# 2019.net
KiCad netlist of a schematic drawn in Altium Designer
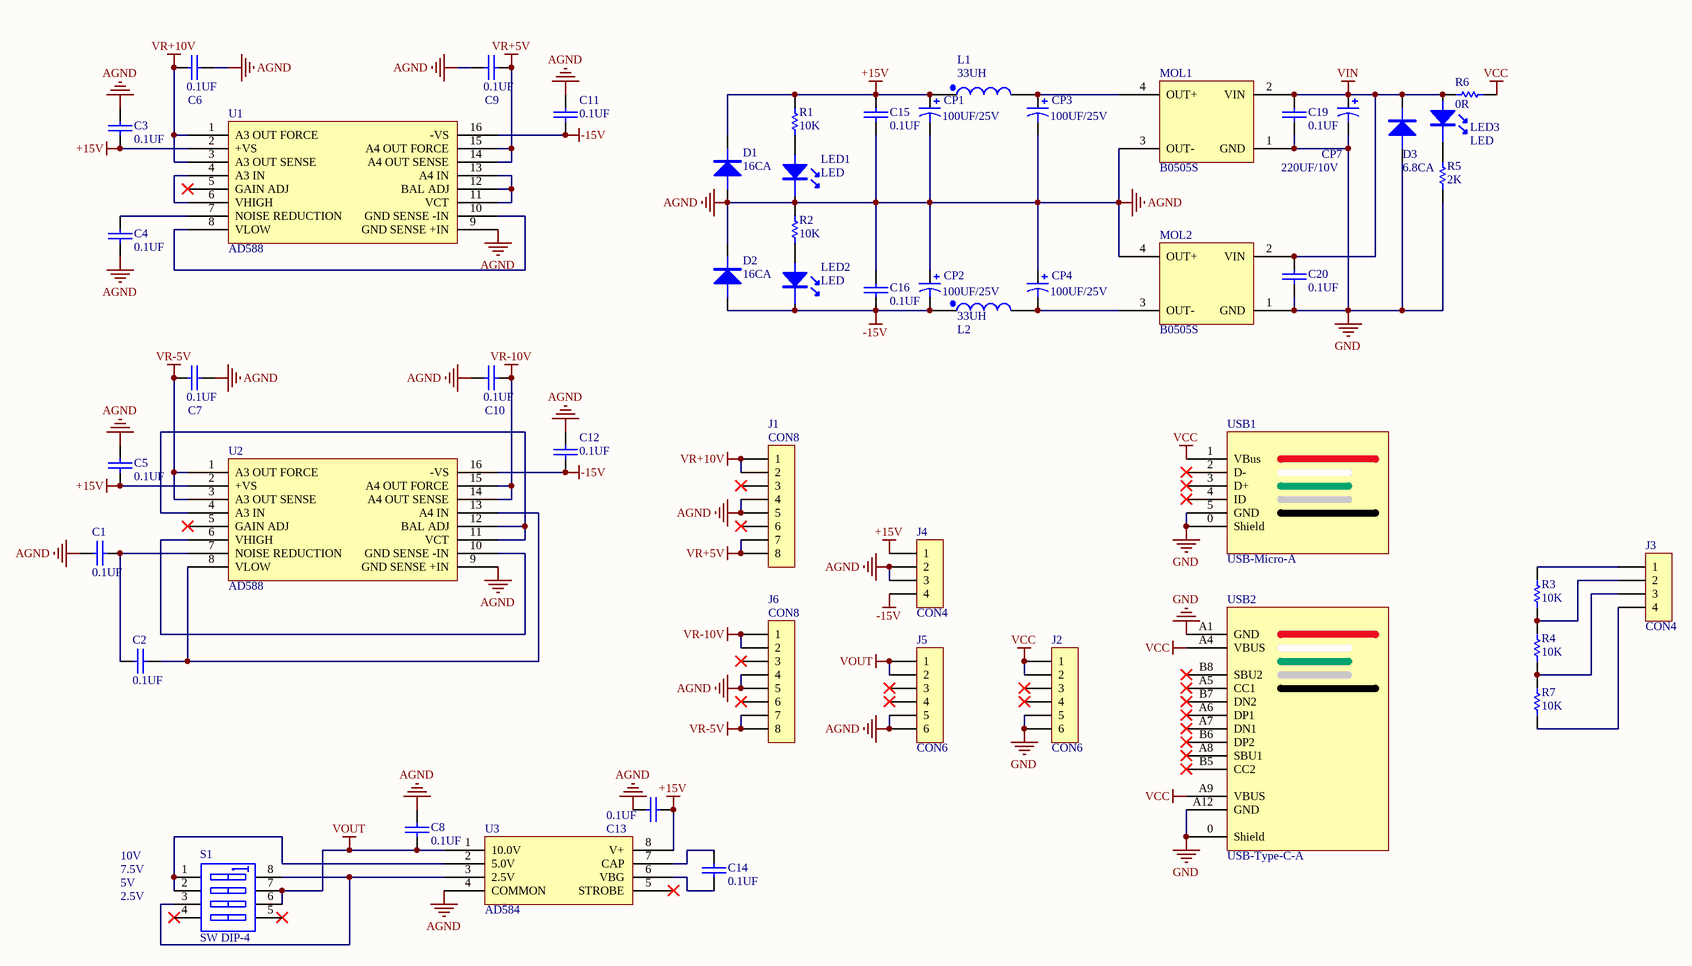
[diagram p0: 2019电压基准.SchDoc]

(export (version "E")
  (design (tool "Eeschema 10.0.6"))
  (components
    (comp (ref "C1") (value "0.1UF") (footprint "cap-3") (libsource (lib "原理图库") (part "CAP")))
    (comp (ref "C2") (value "0.1UF") (footprint "cap-3") (libsource (lib "原理图库") (part "CAP")))
    (comp (ref "C3") (value "0.1UF") (footprint "CAP-3") (libsource (lib "原理图库") (part "CAP")))
    (comp (ref "C4") (value "0.1UF") (footprint "CAP-3") (libsource (lib "原理图库") (part "CAP")))
    (comp (ref "C5") (value "0.1UF") (footprint "cap-3") (libsource (lib "原理图库") (part "CAP")))
    (comp (ref "C6") (value "0.1UF") (footprint "CAP-3") (libsource (lib "原理图库") (part "CAP")))
    (comp (ref "C7") (value "0.1UF") (footprint "CAP-3") (libsource (lib "原理图库") (part "CAP")))
    (comp (ref "C8") (value "0.1UF") (footprint "CAP-3") (libsource (lib "原理图库") (part "CAP")))
    (comp (ref "C9") (value "0.1UF") (footprint "CAP-3") (libsource (lib "原理图库") (part "CAP")))
    (comp (ref "C10") (value "0.1UF") (footprint "CAP-3") (libsource (lib "原理图库") (part "CAP")))
    (comp (ref "C11") (value "0.1UF") (footprint "CAP-3") (libsource (lib "原理图库") (part "CAP")))
    (comp (ref "C12") (value "0.1UF") (footprint "cap-3") (libsource (lib "原理图库") (part "CAP")))
    (comp (ref "C13") (value "0.1UF") (footprint "CAP-3") (libsource (lib "原理图库") (part "CAP")))
    (comp (ref "C14") (value "0.1UF") (footprint "cap-3") (libsource (lib "原理图库") (part "CAP")))
    (comp (ref "C15") (value "0.1UF") (footprint "LC-0603-C") (libsource (lib "原理图库") (part "CAP")))
    (comp (ref "C16") (value "0.1UF") (footprint "LC-0603-C") (libsource (lib "原理图库") (part "CAP")))
    (comp (ref "C19") (value "0.1UF") (footprint "LC-0603-C") (libsource (lib "原理图库") (part "CAP")))
    (comp (ref "C20") (value "0.1UF") (footprint "LC-0603-C") (libsource (lib "原理图库") (part "CAP")))
    (comp (ref "CP1") (value "100UF/25V") (footprint "cap") (libsource (lib "原理图库") (part "CAP1")))
    (comp (ref "CP2") (value "100UF/25V") (footprint "cap") (libsource (lib "原理图库") (part "CAP1")))
    (comp (ref "CP3") (value "100UF/25V") (footprint "cap") (libsource (lib "原理图库") (part "CAP1")))
    (comp (ref "CP4") (value "100UF/25V") (footprint "cap") (libsource (lib "原理图库") (part "CAP1")))
    (comp (ref "CP7") (value "220UF/10V") (footprint "cap") (libsource (lib "原理图库") (part "CAP1")))
    (comp (ref "D1")
      (value "16CA")
      (footprint "LC-SMA(DO-214AC)_S3")
      (libsource (lib "原理图库.坏") (part "DIODE"))
    )
    (comp (ref "D2")
      (value "16CA")
      (footprint "LC-SMA(DO-214AC)_S3")
      (libsource (lib "原理图库.坏") (part "DIODE"))
    )
    (comp (ref "D3")
      (value "6.8CA")
      (footprint "LC-SMA(DO-214AC)_S3")
      (libsource (lib "原理图库.坏") (part "DIODE"))
    )
    (comp (ref "J1")
      (value "CON8")
      (footprint "sip-8")
      (description "Connector")
      (libsource (lib "接插件") (part "CON8"))
    )
    (comp (ref "J2")
      (value "CON6")
      (footprint "sip-6")
      (description "Connector")
      (libsource (lib "接插件") (part "CON6"))
    )
    (comp (ref "J3")
      (value "CON4")
      (footprint "sip-4")
      (description "Connector")
      (libsource (lib "接插件") (part "CON4"))
    )
    (comp (ref "J4")
      (value "CON4")
      (footprint "sip-4")
      (description "Connector")
      (libsource (lib "接插件") (part "CON4"))
    )
    (comp (ref "J5")
      (value "CON6")
      (footprint "sip-6")
      (description "Connector")
      (libsource (lib "接插件") (part "CON6"))
    )
    (comp (ref "J6")
      (value "CON8")
      (footprint "sip-8")
      (description "Connector")
      (libsource (lib "接插件") (part "CON8"))
    )
    (comp (ref "L1") (value "33UH") (footprint "lin6*6") (libsource (lib "原理图库") (part "INDUCTOR")))
    (comp (ref "L2") (value "33UH") (footprint "lin6*6") (libsource (lib "原理图库") (part "INDUCTOR")))
    (comp (ref "LED1") (value "LED") (footprint "lc-0603_LED_S5") (libsource (lib "原理图库.坏") (part "LED")))
    (comp (ref "LED2") (value "LED") (footprint "lc-0603_LED_S5") (libsource (lib "原理图库.坏") (part "LED")))
    (comp (ref "LED3") (value "LED") (footprint "lc-0603_LED_S5") (libsource (lib "原理图库.坏") (part "LED")))
    (comp (ref "MOL1") (value "B0505S") (footprint "B0505S") (libsource (lib "原理图库.坏") (part "B0505S")))
    (comp (ref "MOL2") (value "B0505S") (footprint "B0505S") (libsource (lib "原理图库.坏") (part "B0505S")))
    (comp (ref "R1") (value "10K") (footprint "LC-0603-R") (libsource (lib "原理图库") (part "RES")))
    (comp (ref "R2") (value "10K") (footprint "LC-0603-R") (libsource (lib "原理图库") (part "RES")))
    (comp (ref "R3") (value "10K") (footprint "fuse4") (libsource (lib "原理图库") (part "RES")))
    (comp (ref "R4") (value "10K") (footprint "fuse4") (libsource (lib "原理图库") (part "RES")))
    (comp (ref "R5") (value "2K") (footprint "LC-0603-R") (libsource (lib "原理图库") (part "RES")))
    (comp (ref "R6") (value "0R") (footprint "LC-0805_L") (libsource (lib "原理图库") (part "RES")))
    (comp (ref "R7") (value "10K") (footprint "fuse4") (libsource (lib "原理图库") (part "RES")))
    (comp (ref "S1")
      (value "SW DIP-4")
      (footprint "stc-dip8-smd")
      (description "DIP Switch")
      (libsource (lib "接插件") (part "SW DIP-4"))
    )
    (comp (ref "U1") (value "AD588") (footprint "stc-dip16") (libsource (lib "原理图库.坏") (part "AD588")))
    (comp (ref "U2") (value "AD588") (footprint "stc-dip16") (libsource (lib "原理图库.坏") (part "AD588")))
    (comp (ref "U3") (value "AD584") (footprint "stc-dip8") (libsource (lib "原理图库.坏") (part "AD584")))
    (comp (ref "USB1")
      (value "USB-Micro-A")
      (footprint "USB-MICRO-R")
      (libsource (lib "USBSch") (part "USB-Micro-A"))
    )
    (comp (ref "USB2")
      (value "USB-Type-C-A")
      (footprint "USB-Type-C-R")
      (libsource (lib "USBSch") (part "USB-Type-C-A"))
    )
  )
  (nets
    (net (code "1") (name "+15V") (class "Default")
      (node (ref "C13") (pin "1") (pinfunction "1_1") (pintype "passive"))
      (node (ref "C15") (pin "2") (pinfunction "2_2") (pintype "passive"))
      (node (ref "C3") (pin "1") (pinfunction "1_1") (pintype "passive"))
      (node (ref "C5") (pin "1") (pinfunction "1_1") (pintype "passive"))
      (node (ref "CP1") (pin "1") (pinfunction "1_1") (pintype "passive"))
      (node (ref "D1") (pin "2") (pinfunction "2_2") (pintype "passive"))
      (node (ref "J4") (pin "1") (pinfunction "1_1") (pintype "passive"))
      (node (ref "L1") (pin "1") (pinfunction "1_1") (pintype "passive"))
      (node (ref "R1") (pin "1") (pinfunction "1_1") (pintype "passive"))
      (node (ref "U1") (pin "2") (pinfunction "+VS_2") (pintype "passive"))
      (node (ref "U2") (pin "2") (pinfunction "+VS_2") (pintype "passive"))
      (node (ref "U3") (pin "8") (pinfunction "V+_8") (pintype "passive"))
    )
    (net (code "2") (name "-15V") (class "Default")
      (node (ref "C11") (pin "1") (pinfunction "1_1") (pintype "passive"))
      (node (ref "C12") (pin "1") (pinfunction "1_1") (pintype "passive"))
      (node (ref "C16") (pin "1") (pinfunction "1_1") (pintype "passive"))
      (node (ref "CP2") (pin "2") (pinfunction "2_2") (pintype "passive"))
      (node (ref "D2") (pin "1") (pinfunction "1_1") (pintype "passive"))
      (node (ref "J4") (pin "4") (pinfunction "4_4") (pintype "passive"))
      (node (ref "L2") (pin "1") (pinfunction "1_1") (pintype "passive"))
      (node (ref "LED2") (pin "K") (pinfunction "K_K") (pintype "passive"))
      (node (ref "U1") (pin "16") (pinfunction "-VS_16") (pintype "passive"))
      (node (ref "U2") (pin "16") (pinfunction "-VS_16") (pintype "passive"))
    )
    (net (code "3") (name "AGND") (class "Default")
      (node (ref "C1") (pin "1") (pinfunction "1_1") (pintype "passive"))
      (node (ref "C10") (pin "2") (pinfunction "2_2") (pintype "passive"))
      (node (ref "C11") (pin "2") (pinfunction "2_2") (pintype "passive"))
      (node (ref "C12") (pin "2") (pinfunction "2_2") (pintype "passive"))
      (node (ref "C13") (pin "2") (pinfunction "2_2") (pintype "passive"))
      (node (ref "C15") (pin "1") (pinfunction "1_1") (pintype "passive"))
      (node (ref "C16") (pin "2") (pinfunction "2_2") (pintype "passive"))
      (node (ref "C3") (pin "2") (pinfunction "2_2") (pintype "passive"))
      (node (ref "C4") (pin "1") (pinfunction "1_1") (pintype "passive"))
      (node (ref "C5") (pin "2") (pinfunction "2_2") (pintype "passive"))
      (node (ref "C6") (pin "1") (pinfunction "1_1") (pintype "passive"))
      (node (ref "C7") (pin "2") (pinfunction "2_2") (pintype "passive"))
      (node (ref "C8") (pin "1") (pinfunction "1_1") (pintype "passive"))
      (node (ref "C9") (pin "2") (pinfunction "2_2") (pintype "passive"))
      (node (ref "CP1") (pin "2") (pinfunction "2_2") (pintype "passive"))
      (node (ref "CP2") (pin "1") (pinfunction "1_1") (pintype "passive"))
      (node (ref "CP3") (pin "2") (pinfunction "2_2") (pintype "passive"))
      (node (ref "CP4") (pin "1") (pinfunction "1_1") (pintype "passive"))
      (node (ref "D1") (pin "1") (pinfunction "1_1") (pintype "passive"))
      (node (ref "D2") (pin "2") (pinfunction "2_2") (pintype "passive"))
      (node (ref "J1") (pin "4") (pinfunction "4_4") (pintype "passive"))
      (node (ref "J1") (pin "5") (pinfunction "5_5") (pintype "passive"))
      (node (ref "J4") (pin "2") (pinfunction "2_2") (pintype "passive"))
      (node (ref "J4") (pin "3") (pinfunction "3_3") (pintype "passive"))
      (node (ref "J5") (pin "5") (pinfunction "5_5") (pintype "passive"))
      (node (ref "J5") (pin "6") (pinfunction "6_6") (pintype "passive"))
      (node (ref "J6") (pin "4") (pinfunction "4_4") (pintype "passive"))
      (node (ref "J6") (pin "5") (pinfunction "5_5") (pintype "passive"))
      (node (ref "LED1") (pin "K") (pinfunction "K_K") (pintype "passive"))
      (node (ref "MOL1") (pin "3") (pinfunction "OUT-_3") (pintype "passive"))
      (node (ref "MOL2") (pin "4") (pinfunction "OUT+_4") (pintype "passive"))
      (node (ref "R2") (pin "1") (pinfunction "1_1") (pintype "passive"))
      (node (ref "U1") (pin "9") (pinfunction "GND_SENSE_+IN_9") (pintype "passive"))
      (node (ref "U2") (pin "9") (pinfunction "GND_SENSE_+IN_9") (pintype "passive"))
      (node (ref "U3") (pin "4") (pinfunction "COMMON_4") (pintype "passive"))
    )
    (net (code "4") (name "GND") (class "Default")
      (node (ref "C19") (pin "1") (pinfunction "1_1") (pintype "passive"))
      (node (ref "C20") (pin "1") (pinfunction "1_1") (pintype "passive"))
      (node (ref "CP7") (pin "2") (pinfunction "2_2") (pintype "passive"))
      (node (ref "D3") (pin "1") (pinfunction "1_1") (pintype "passive"))
      (node (ref "J2") (pin "5") (pinfunction "5_5") (pintype "passive"))
      (node (ref "J2") (pin "6") (pinfunction "6_6") (pintype "passive"))
      (node (ref "MOL1") (pin "1") (pinfunction "GND_1") (pintype "passive"))
      (node (ref "MOL2") (pin "1") (pinfunction "GND_1") (pintype "passive"))
      (node (ref "R5") (pin "1") (pinfunction "1_1") (pintype "passive"))
      (node (ref "USB1") (pin "0") (pinfunction "Shield_0") (pintype "passive"))
      (node (ref "USB1") (pin "5") (pinfunction "GND_5") (pintype "passive"))
      (node (ref "USB2") (pin "0") (pinfunction "Shield_0") (pintype "passive"))
      (node (ref "USB2") (pin "A1") (pinfunction "GND_A1") (pintype "passive"))
      (node (ref "USB2") (pin "A12") (pinfunction "GND_A12") (pintype "passive"))
    )
    (net (code "5") (name "Net-(J3-Pad1)") (class "Default")
      (node (ref "J3") (pin "1") (pinfunction "1_1") (pintype "passive"))
      (node (ref "R3") (pin "2") (pinfunction "2_2") (pintype "passive"))
    )
    (net (code "6") (name "Net-(J3-Pad2)") (class "Default")
      (node (ref "J3") (pin "2") (pinfunction "2_2") (pintype "passive"))
      (node (ref "R3") (pin "1") (pinfunction "1_1") (pintype "passive"))
      (node (ref "R4") (pin "2") (pinfunction "2_2") (pintype "passive"))
    )
    (net (code "7") (name "Net-(J3-Pad3)") (class "Default")
      (node (ref "J3") (pin "3") (pinfunction "3_3") (pintype "passive"))
      (node (ref "R4") (pin "1") (pinfunction "1_1") (pintype "passive"))
      (node (ref "R7") (pin "2") (pinfunction "2_2") (pintype "passive"))
    )
    (net (code "8") (name "Net-(J3-Pad4)") (class "Default")
      (node (ref "J3") (pin "4") (pinfunction "4_4") (pintype "passive"))
      (node (ref "R7") (pin "1") (pinfunction "1_1") (pintype "passive"))
    )
    (net (code "9") (name "Net-(LED1-PadA)") (class "Default")
      (node (ref "LED1") (pin "A") (pinfunction "A_A") (pintype "passive"))
      (node (ref "R1") (pin "2") (pinfunction "2_2") (pintype "passive"))
    )
    (net (code "10") (name "Net-(LED2-PadA)") (class "Default")
      (node (ref "LED2") (pin "A") (pinfunction "A_A") (pintype "passive"))
      (node (ref "R2") (pin "2") (pinfunction "2_2") (pintype "passive"))
    )
    (net (code "11") (name "Net-(LED3-PadK)") (class "Default")
      (node (ref "LED3") (pin "K") (pinfunction "K_K") (pintype "passive"))
      (node (ref "R5") (pin "2") (pinfunction "2_2") (pintype "passive"))
    )
    (net (code "12") (name "Net-(MOL1-OUT+)") (class "Default")
      (node (ref "CP3") (pin "1") (pinfunction "1_1") (pintype "passive"))
      (node (ref "L1") (pin "2") (pinfunction "2_2") (pintype "passive"))
      (node (ref "MOL1") (pin "4") (pinfunction "OUT+_4") (pintype "passive"))
    )
    (net (code "13") (name "Net-(MOL2-OUT-)") (class "Default")
      (node (ref "CP4") (pin "2") (pinfunction "2_2") (pintype "passive"))
      (node (ref "L2") (pin "2") (pinfunction "2_2") (pintype "passive"))
      (node (ref "MOL2") (pin "3") (pinfunction "OUT-_3") (pintype "passive"))
    )
    (net (code "14") (name "Net-(S1-A1)") (class "Default")
      (node (ref "S1") (pin "1") (pinfunction "A1_1") (pintype "passive"))
      (node (ref "S1") (pin "2") (pinfunction "A2_2") (pintype "passive"))
      (node (ref "U3") (pin "2") (pinfunction "5.0V_2") (pintype "passive"))
    )
    (net (code "15") (name "Net-(S1-A3)") (class "Default")
      (node (ref "S1") (pin "3") (pinfunction "A3_3") (pintype "passive"))
      (node (ref "S1") (pin "8") (pinfunction "B1_8") (pintype "passive"))
      (node (ref "U3") (pin "3") (pinfunction "2.5V_3") (pintype "passive"))
    )
    (net (code "16") (name "Net-(U1-A3_IN)") (class "Default")
      (node (ref "U1") (pin "4") (pinfunction "A3_IN_4") (pintype "passive"))
      (node (ref "U1") (pin "6") (pinfunction "VHIGH_6") (pintype "passive"))
    )
    (net (code "17") (name "Net-(U1-A4_IN)") (class "Default")
      (node (ref "U1") (pin "11") (pinfunction "VCT_11") (pintype "passive"))
      (node (ref "U1") (pin "12") (pinfunction "BAL_ADJ_12") (pintype "passive"))
      (node (ref "U1") (pin "13") (pinfunction "A4_IN_13") (pintype "passive"))
    )
    (net (code "18") (name "Net-(U1-GND_SENSE_-IN)") (class "Default")
      (node (ref "U1") (pin "10") (pinfunction "GND_SENSE_-IN_10") (pintype "passive"))
      (node (ref "U1") (pin "8") (pinfunction "VLOW_8") (pintype "passive"))
    )
    (net (code "19") (name "Net-(U1-NOISE_REDUCTION)") (class "Default")
      (node (ref "C4") (pin "2") (pinfunction "2_2") (pintype "passive"))
      (node (ref "U1") (pin "7") (pinfunction "NOISE_REDUCTION_7") (pintype "passive"))
    )
    (net (code "20") (name "Net-(U2-A3_IN)") (class "Default")
      (node (ref "U2") (pin "11") (pinfunction "VCT_11") (pintype "passive"))
      (node (ref "U2") (pin "12") (pinfunction "BAL_ADJ_12") (pintype "passive"))
      (node (ref "U2") (pin "4") (pinfunction "A3_IN_4") (pintype "passive"))
    )
    (net (code "21") (name "Net-(U2-A4_IN)") (class "Default")
      (node (ref "C2") (pin "1") (pinfunction "1_1") (pintype "passive"))
      (node (ref "U2") (pin "13") (pinfunction "A4_IN_13") (pintype "passive"))
      (node (ref "U2") (pin "8") (pinfunction "VLOW_8") (pintype "passive"))
    )
    (net (code "22") (name "Net-(U2-GND_SENSE_-IN)") (class "Default")
      (node (ref "U2") (pin "10") (pinfunction "GND_SENSE_-IN_10") (pintype "passive"))
      (node (ref "U2") (pin "6") (pinfunction "VHIGH_6") (pintype "passive"))
    )
    (net (code "23") (name "Net-(U2-NOISE_REDUCTION)") (class "Default")
      (node (ref "C1") (pin "2") (pinfunction "2_2") (pintype "passive"))
      (node (ref "C2") (pin "2") (pinfunction "2_2") (pintype "passive"))
      (node (ref "U2") (pin "7") (pinfunction "NOISE_REDUCTION_7") (pintype "passive"))
    )
    (net (code "24") (name "Net-(U3-CAP)") (class "Default")
      (node (ref "C14") (pin "1") (pinfunction "1_1") (pintype "passive"))
      (node (ref "U3") (pin "7") (pinfunction "CAP_7") (pintype "passive"))
    )
    (net (code "25") (name "Net-(U3-VBG)") (class "Default")
      (node (ref "C14") (pin "2") (pinfunction "2_2") (pintype "passive"))
      (node (ref "U3") (pin "6") (pinfunction "VBG_6") (pintype "passive"))
    )
    (net (code "26") (name "VCC") (class "Default")
      (node (ref "J2") (pin "1") (pinfunction "1_1") (pintype "passive"))
      (node (ref "J2") (pin "2") (pinfunction "2_2") (pintype "passive"))
      (node (ref "R6") (pin "1") (pinfunction "1_1") (pintype "passive"))
      (node (ref "USB1") (pin "1") (pinfunction "VBus_1") (pintype "passive"))
      (node (ref "USB2") (pin "A4") (pinfunction "VBUS_A4") (pintype "passive"))
      (node (ref "USB2") (pin "A9") (pinfunction "VBUS_A9") (pintype "passive"))
    )
    (net (code "27") (name "VIN") (class "Default")
      (node (ref "C19") (pin "2") (pinfunction "2_2") (pintype "passive"))
      (node (ref "C20") (pin "2") (pinfunction "2_2") (pintype "passive"))
      (node (ref "CP7") (pin "1") (pinfunction "1_1") (pintype "passive"))
      (node (ref "D3") (pin "2") (pinfunction "2_2") (pintype "passive"))
      (node (ref "LED3") (pin "A") (pinfunction "A_A") (pintype "passive"))
      (node (ref "MOL1") (pin "2") (pinfunction "VIN_2") (pintype "passive"))
      (node (ref "MOL2") (pin "2") (pinfunction "VIN_2") (pintype "passive"))
      (node (ref "R6") (pin "2") (pinfunction "2_2") (pintype "passive"))
    )
    (net (code "28") (name "VOUT") (class "Default")
      (node (ref "C8") (pin "2") (pinfunction "2_2") (pintype "passive"))
      (node (ref "J5") (pin "1") (pinfunction "1_1") (pintype "passive"))
      (node (ref "J5") (pin "2") (pinfunction "2_2") (pintype "passive"))
      (node (ref "S1") (pin "6") (pinfunction "B3_6") (pintype "passive"))
      (node (ref "S1") (pin "7") (pinfunction "B2_7") (pintype "passive"))
      (node (ref "U3") (pin "1") (pinfunction "10.0V_1") (pintype "passive"))
    )
    (net (code "29") (name "VR+5V") (class "Default")
      (node (ref "C9") (pin "1") (pinfunction "1_1") (pintype "passive"))
      (node (ref "J1") (pin "7") (pinfunction "7_7") (pintype "passive"))
      (node (ref "J1") (pin "8") (pinfunction "8_8") (pintype "passive"))
      (node (ref "U1") (pin "14") (pinfunction "A4_OUT_SENSE_14") (pintype "passive"))
      (node (ref "U1") (pin "15") (pinfunction "A4_OUT_FORCE_15") (pintype "passive"))
    )
    (net (code "30") (name "VR+10V") (class "Default")
      (node (ref "C6") (pin "2") (pinfunction "2_2") (pintype "passive"))
      (node (ref "J1") (pin "1") (pinfunction "1_1") (pintype "passive"))
      (node (ref "J1") (pin "2") (pinfunction "2_2") (pintype "passive"))
      (node (ref "U1") (pin "1") (pinfunction "A3_OUT_FORCE_1") (pintype "passive"))
      (node (ref "U1") (pin "3") (pinfunction "A3_OUT_SENSE_3") (pintype "passive"))
    )
    (net (code "31") (name "VR-5V") (class "Default")
      (node (ref "C7") (pin "1") (pinfunction "1_1") (pintype "passive"))
      (node (ref "J6") (pin "7") (pinfunction "7_7") (pintype "passive"))
      (node (ref "J6") (pin "8") (pinfunction "8_8") (pintype "passive"))
      (node (ref "U2") (pin "1") (pinfunction "A3_OUT_FORCE_1") (pintype "passive"))
      (node (ref "U2") (pin "3") (pinfunction "A3_OUT_SENSE_3") (pintype "passive"))
    )
    (net (code "32") (name "VR-10V") (class "Default")
      (node (ref "C10") (pin "1") (pinfunction "1_1") (pintype "passive"))
      (node (ref "J6") (pin "1") (pinfunction "1_1") (pintype "passive"))
      (node (ref "J6") (pin "2") (pinfunction "2_2") (pintype "passive"))
      (node (ref "U2") (pin "14") (pinfunction "A4_OUT_SENSE_14") (pintype "passive"))
      (node (ref "U2") (pin "15") (pinfunction "A4_OUT_FORCE_15") (pintype "passive"))
    )
    (net (code "33") (name "unconnected-(J1-Pad3)") (class "Default")
      (node (ref "J1") (pin "3") (pinfunction "3_3") (pintype "passive+no_connect"))
    )
    (net (code "34") (name "unconnected-(J1-Pad6)") (class "Default")
      (node (ref "J1") (pin "6") (pinfunction "6_6") (pintype "passive+no_connect"))
    )
    (net (code "35") (name "unconnected-(J2-Pad3)") (class "Default")
      (node (ref "J2") (pin "3") (pinfunction "3_3") (pintype "passive+no_connect"))
    )
    (net (code "36") (name "unconnected-(J2-Pad4)") (class "Default")
      (node (ref "J2") (pin "4") (pinfunction "4_4") (pintype "passive+no_connect"))
    )
    (net (code "37") (name "unconnected-(J5-Pad3)") (class "Default")
      (node (ref "J5") (pin "3") (pinfunction "3_3") (pintype "passive+no_connect"))
    )
    (net (code "38") (name "unconnected-(J5-Pad4)") (class "Default")
      (node (ref "J5") (pin "4") (pinfunction "4_4") (pintype "passive+no_connect"))
    )
    (net (code "39") (name "unconnected-(J6-Pad3)") (class "Default")
      (node (ref "J6") (pin "3") (pinfunction "3_3") (pintype "passive+no_connect"))
    )
    (net (code "40") (name "unconnected-(J6-Pad6)") (class "Default")
      (node (ref "J6") (pin "6") (pinfunction "6_6") (pintype "passive+no_connect"))
    )
    (net (code "41") (name "unconnected-(S1-A4-Pad4)") (class "Default")
      (node (ref "S1") (pin "4") (pinfunction "A4_4") (pintype "passive+no_connect"))
    )
    (net (code "42") (name "unconnected-(S1-B4-Pad5)") (class "Default")
      (node (ref "S1") (pin "5") (pinfunction "B4_5") (pintype "passive+no_connect"))
    )
    (net (code "43") (name "unconnected-(U1-GAIN_ADJ-Pad5)") (class "Default")
      (node (ref "U1") (pin "5") (pinfunction "GAIN_ADJ_5") (pintype "passive+no_connect"))
    )
    (net (code "44") (name "unconnected-(U2-GAIN_ADJ-Pad5)") (class "Default")
      (node (ref "U2") (pin "5") (pinfunction "GAIN_ADJ_5") (pintype "passive+no_connect"))
    )
    (net (code "45") (name "unconnected-(U3-STROBE-Pad5)") (class "Default")
      (node (ref "U3") (pin "5") (pinfunction "STROBE_5") (pintype "passive+no_connect"))
    )
    (net (code "46") (name "unconnected-(USB1-D+-Pad3)") (class "Default")
      (node (ref "USB1") (pin "3") (pinfunction "D+_3") (pintype "passive+no_connect"))
    )
    (net (code "47") (name "unconnected-(USB1-D--Pad2)") (class "Default")
      (node (ref "USB1") (pin "2") (pinfunction "D-_2") (pintype "passive+no_connect"))
    )
    (net (code "48") (name "unconnected-(USB1-ID-Pad4)") (class "Default")
      (node (ref "USB1") (pin "4") (pinfunction "ID_4") (pintype "passive+no_connect"))
    )
    (net (code "49") (name "unconnected-(USB2-CC1-PadA5)") (class "Default")
      (node (ref "USB2") (pin "A5") (pinfunction "CC1_A5") (pintype "passive+no_connect"))
    )
    (net (code "50") (name "unconnected-(USB2-CC2-PadB5)") (class "Default")
      (node (ref "USB2") (pin "B5") (pinfunction "CC2_B5") (pintype "passive+no_connect"))
    )
    (net (code "51") (name "unconnected-(USB2-DN1-PadA7)") (class "Default")
      (node (ref "USB2") (pin "A7") (pinfunction "DN1_A7") (pintype "passive+no_connect"))
    )
    (net (code "52") (name "unconnected-(USB2-DN2-PadB7)") (class "Default")
      (node (ref "USB2") (pin "B7") (pinfunction "DN2_B7") (pintype "passive+no_connect"))
    )
    (net (code "53") (name "unconnected-(USB2-DP1-PadA6)") (class "Default")
      (node (ref "USB2") (pin "A6") (pinfunction "DP1_A6") (pintype "passive+no_connect"))
    )
    (net (code "54") (name "unconnected-(USB2-DP2-PadB6)") (class "Default")
      (node (ref "USB2") (pin "B6") (pinfunction "DP2_B6") (pintype "passive+no_connect"))
    )
    (net (code "55") (name "unconnected-(USB2-SBU1-PadA8)") (class "Default")
      (node (ref "USB2") (pin "A8") (pinfunction "SBU1_A8") (pintype "passive+no_connect"))
    )
    (net (code "56") (name "unconnected-(USB2-SBU2-PadB8)") (class "Default")
      (node (ref "USB2") (pin "B8") (pinfunction "SBU2_B8") (pintype "passive+no_connect"))
    )
  )
)
